# 04_KEY.net
KiCad netlist of a schematic drawn in Altium Designer
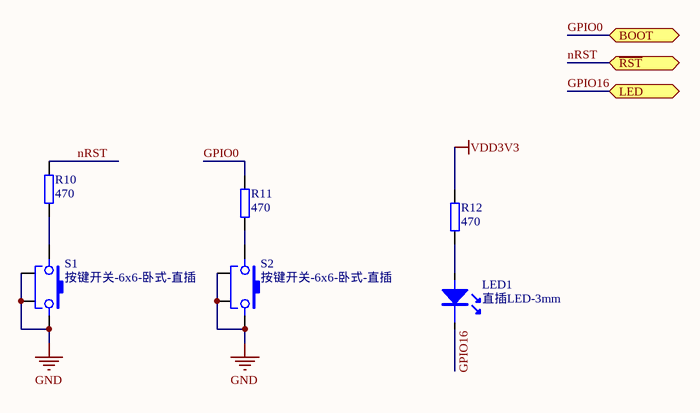
[diagram p0: 04_KEY.SchDoc]

(export (version "E")
  (design (tool "Eeschema 10.0.6"))
  (components
    (comp (ref "LED1")
      (value "直插LED-3mm")
      (footprint "直插LED-3mm")
      (libsource (lib "Vowstar_Basic_Device") (part "直插LED-3mm"))
    )
    (comp (ref "R10")
      (value "470")
      (footprint "SMT_R_0402")
      (description "Surface mount resistor 0402")
      (libsource (lib "Vowstar_Basic_Device") (part "SMT_R_0402"))
    )
    (comp (ref "R11")
      (value "470")
      (footprint "SMT_R_0402")
      (description "Surface mount resistor 0402")
      (libsource (lib "Vowstar_Basic_Device") (part "SMT_R_0402"))
    )
    (comp (ref "R12")
      (value "470")
      (footprint "SMT_R_0402")
      (description "Surface mount resistor 0402")
      (libsource (lib "Vowstar_Basic_Device") (part "SMT_R_0402"))
    )
    (comp (ref "S1")
      (value "按键开关-6x6-卧式-直插")
      (footprint "按键开关-6x6-卧式-直插")
      (libsource (lib "Vowstar_Switch") (part "按键开关-6x6-卧式-直插"))
    )
    (comp (ref "S2")
      (value "按键开关-6x6-卧式-直插")
      (footprint "按键开关-6x6-卧式-直插")
      (libsource (lib "Vowstar_Switch") (part "按键开关-6x6-卧式-直插"))
    )
  )
  (nets
    (net (code "1") (name "/GPIO0") (class "Default")
      (node (ref "R11") (pin "2") (pinfunction "2_2") (pintype "passive"))
    )
    (net (code "2") (name "/GPIO16") (class "Default")
      (node (ref "LED1") (pin "2") (pinfunction "K_2") (pintype "passive"))
    )
    (net (code "3") (name "/nRST") (class "Default")
      (node (ref "R10") (pin "2") (pinfunction "2_2") (pintype "passive"))
    )
    (net (code "4") (name "GND") (class "Default")
      (node (ref "S1") (pin "2") (pinfunction "PIN2_2") (pintype "passive"))
      (node (ref "S1") (pin "3") (pinfunction "3_3") (pintype "passive"))
      (node (ref "S1") (pin "4") (pinfunction "4_4") (pintype "passive"))
      (node (ref "S2") (pin "2") (pinfunction "PIN2_2") (pintype "passive"))
      (node (ref "S2") (pin "3") (pinfunction "3_3") (pintype "passive"))
      (node (ref "S2") (pin "4") (pinfunction "4_4") (pintype "passive"))
    )
    (net (code "5") (name "Net-(LED1-A)") (class "Default")
      (node (ref "LED1") (pin "1") (pinfunction "A_1") (pintype "passive"))
      (node (ref "R12") (pin "2") (pinfunction "2_2") (pintype "passive"))
    )
    (net (code "6") (name "Net-(S1-PIN1)") (class "Default")
      (node (ref "R10") (pin "1") (pinfunction "1_1") (pintype "passive"))
      (node (ref "S1") (pin "1") (pinfunction "PIN1_1") (pintype "passive"))
    )
    (net (code "7") (name "Net-(S2-PIN1)") (class "Default")
      (node (ref "R11") (pin "1") (pinfunction "1_1") (pintype "passive"))
      (node (ref "S2") (pin "1") (pinfunction "PIN1_1") (pintype "passive"))
    )
    (net (code "8") (name "VDD3V3") (class "Default")
      (node (ref "R12") (pin "1") (pinfunction "1_1") (pintype "passive"))
    )
  )
)
